# Computation.net
KiCad netlist of a schematic drawn in Altium Designer
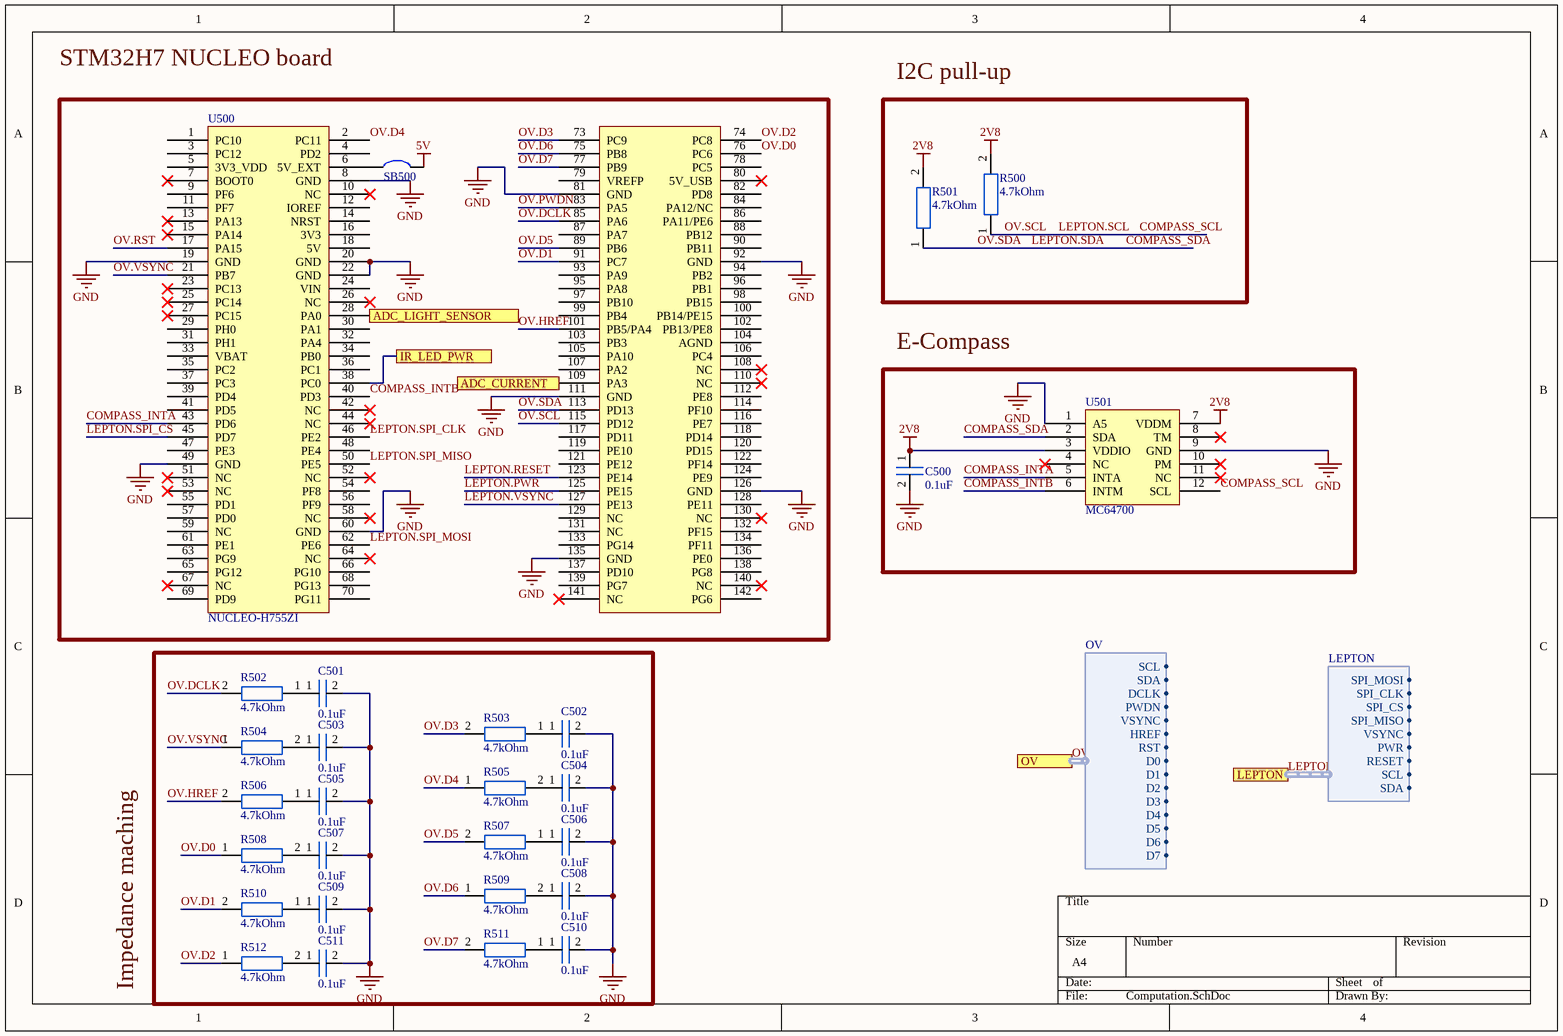
[diagram p0: Computation.SchDoc]

(export (version "E")
  (design (tool "Eeschema 10.0.6"))
  (components
    (comp (ref "C500")
      (value "0.1uF")
      (footprint "0402_footprint")
      (description "0402 capacitor")
      (libsource (lib "Schlib1") (part "Capacitor_0402"))
    )
    (comp (ref "C501")
      (value "0.1uF")
      (footprint "0402_footprint")
      (description "0402 capacitor")
      (libsource (lib "Schlib1") (part "Capacitor_0402"))
    )
    (comp (ref "C502")
      (value "0.1uF")
      (footprint "0402_footprint")
      (description "0402 capacitor")
      (libsource (lib "Schlib1") (part "Capacitor_0402"))
    )
    (comp (ref "C503")
      (value "0.1uF")
      (footprint "0402_footprint")
      (description "0402 capacitor")
      (libsource (lib "Schlib1") (part "Capacitor_0402"))
    )
    (comp (ref "C504")
      (value "0.1uF")
      (footprint "0402_footprint")
      (description "0402 capacitor")
      (libsource (lib "Schlib1") (part "Capacitor_0402"))
    )
    (comp (ref "C505")
      (value "0.1uF")
      (footprint "0402_footprint")
      (description "0402 capacitor")
      (libsource (lib "Schlib1") (part "Capacitor_0402"))
    )
    (comp (ref "C506")
      (value "0.1uF")
      (footprint "0402_footprint")
      (description "0402 capacitor")
      (libsource (lib "Schlib1") (part "Capacitor_0402"))
    )
    (comp (ref "C507")
      (value "0.1uF")
      (footprint "0402_footprint")
      (description "0402 capacitor")
      (libsource (lib "Schlib1") (part "Capacitor_0402"))
    )
    (comp (ref "C508")
      (value "0.1uF")
      (footprint "0402_footprint")
      (description "0402 capacitor")
      (libsource (lib "Schlib1") (part "Capacitor_0402"))
    )
    (comp (ref "C509")
      (value "0.1uF")
      (footprint "0402_footprint")
      (description "0402 capacitor")
      (libsource (lib "Schlib1") (part "Capacitor_0402"))
    )
    (comp (ref "C510")
      (value "0.1uF")
      (footprint "0402_footprint")
      (description "0402 capacitor")
      (libsource (lib "Schlib1") (part "Capacitor_0402"))
    )
    (comp (ref "C511")
      (value "0.1uF")
      (footprint "0402_footprint")
      (description "0402 capacitor")
      (libsource (lib "Schlib1") (part "Capacitor_0402"))
    )
    (comp (ref "R500")
      (value "4.7kOhm")
      (footprint "0402_footprint")
      (description "0402 resistor")
      (libsource (lib "Schlib1") (part "Resistor_0402"))
    )
    (comp (ref "R501")
      (value "4.7kOhm")
      (footprint "0402_footprint")
      (description "0402 resistor")
      (libsource (lib "Schlib1") (part "Resistor_0402"))
    )
    (comp (ref "R502")
      (value "4.7kOhm")
      (footprint "0402_footprint")
      (description "0402 resistor")
      (libsource (lib "Schlib1") (part "Resistor_0402"))
    )
    (comp (ref "R503")
      (value "4.7kOhm")
      (footprint "0402_footprint")
      (description "0402 resistor")
      (libsource (lib "Schlib1") (part "Resistor_0402"))
    )
    (comp (ref "R504")
      (value "4.7kOhm")
      (footprint "0402_footprint")
      (description "0402 resistor")
      (libsource (lib "Schlib1") (part "Resistor_0402"))
    )
    (comp (ref "R505")
      (value "4.7kOhm")
      (footprint "0402_footprint")
      (description "0402 resistor")
      (libsource (lib "Schlib1") (part "Resistor_0402"))
    )
    (comp (ref "R506")
      (value "4.7kOhm")
      (footprint "0402_footprint")
      (description "0402 resistor")
      (libsource (lib "Schlib1") (part "Resistor_0402"))
    )
    (comp (ref "R507")
      (value "4.7kOhm")
      (footprint "0402_footprint")
      (description "0402 resistor")
      (libsource (lib "Schlib1") (part "Resistor_0402"))
    )
    (comp (ref "R508")
      (value "4.7kOhm")
      (footprint "0402_footprint")
      (description "0402 resistor")
      (libsource (lib "Schlib1") (part "Resistor_0402"))
    )
    (comp (ref "R509")
      (value "4.7kOhm")
      (footprint "0402_footprint")
      (description "0402 resistor")
      (libsource (lib "Schlib1") (part "Resistor_0402"))
    )
    (comp (ref "R510")
      (value "4.7kOhm")
      (footprint "0402_footprint")
      (description "0402 resistor")
      (libsource (lib "Schlib1") (part "Resistor_0402"))
    )
    (comp (ref "R511")
      (value "4.7kOhm")
      (footprint "0402_footprint")
      (description "0402 resistor")
      (libsource (lib "Schlib1") (part "Resistor_0402"))
    )
    (comp (ref "R512")
      (value "4.7kOhm")
      (footprint "0402_footprint")
      (description "0402 resistor")
      (libsource (lib "Schlib1") (part "Resistor_0402"))
    )
    (comp (ref "SB500")
      (value "Solder_bridge")
      (footprint "SOLDER_BRIDGE")
      (libsource (lib "Schlib1") (part "Solder_bridge"))
    )
    (comp (ref "U500")
      (value "NUCLEO-H755ZI")
      (footprint "H7/H5_NUCLEO_SHIELD")
      (description "https://www.st.com/en/evaluation-tools/nucleo-h755zi-q.html#documentation")
      (libsource (lib "Schlib1") (part "NUCLEO-H755ZI"))
    )
    (comp (ref "U501")
      (value "MC64700")
      (footprint "MC6470")
      (description "6 axis accelerometer + magnetometer")
      (libsource (lib "Schlib1") (part "MC64700"))
    )
  )
  (nets
    (net (code "3") (name "/ADC_CURRENT") (class "Default")
      (node (ref "U500") (pin "109") (pinfunction "PA3_109") (pintype "passive"))
    )
    (net (code "4") (name "/ADC_LIGHT_SENSOR") (class "Default")
      (node (ref "U500") (pin "28") (pinfunction "PA0_28") (pintype "passive"))
    )
    (net (code "5") (name "/COMPASS_INTA") (class "Default")
      (node (ref "U500") (pin "43") (pinfunction "PD6_43") (pintype "passive"))
      (node (ref "U501") (pin "5") (pinfunction "INTA_5") (pintype "passive"))
    )
    (net (code "6") (name "/COMPASS_INTB") (class "Default")
      (node (ref "U500") (pin "40") (pinfunction "PD3_40") (pintype "passive"))
      (node (ref "U501") (pin "6") (pinfunction "INTM_6") (pintype "passive"))
    )
    (net (code "7") (name "/COMPASS_SCL") (class "Default")
      (node (ref "R500") (pin "1") (pinfunction "1_1") (pintype "passive"))
      (node (ref "U500") (pin "115") (pinfunction "PD12_115") (pintype "passive"))
      (node (ref "U501") (pin "12") (pinfunction "SCL_12") (pintype "passive"))
    )
    (net (code "8") (name "/COMPASS_SDA") (class "Default")
      (node (ref "R501") (pin "1") (pinfunction "1_1") (pintype "passive"))
      (node (ref "U500") (pin "113") (pinfunction "PD13_113") (pintype "passive"))
      (node (ref "U501") (pin "2") (pinfunction "SDA_2") (pintype "passive"))
    )
    (net (code "9") (name "/IR_LED_PWR") (class "Default")
      (node (ref "U500") (pin "38") (pinfunction "PC0_38") (pintype "passive"))
    )
    (net (code "10") (name "/LEPTON.PWR") (class "Default")
      (node (ref "U500") (pin "125") (pinfunction "PE15_125") (pintype "passive"))
    )
    (net (code "11") (name "/LEPTON.RESET") (class "Default")
      (node (ref "U500") (pin "123") (pinfunction "PE14_123") (pintype "passive"))
    )
    (net (code "12") (name "/LEPTON.SPI_CLK") (class "Default")
      (node (ref "U500") (pin "46") (pinfunction "PE2_46") (pintype "passive"))
    )
    (net (code "13") (name "/LEPTON.SPI_CS") (class "Default")
      (node (ref "U500") (pin "45") (pinfunction "PD7_45") (pintype "passive"))
    )
    (net (code "14") (name "/LEPTON.SPI_MISO") (class "Default")
      (node (ref "U500") (pin "50") (pinfunction "PE5_50") (pintype "passive"))
    )
    (net (code "15") (name "/LEPTON.SPI_MOSI") (class "Default")
      (node (ref "U500") (pin "62") (pinfunction "PE6_62") (pintype "passive"))
    )
    (net (code "16") (name "/LEPTON.VSYNC") (class "Default")
      (node (ref "U500") (pin "127") (pinfunction "PE13_127") (pintype "passive"))
    )
    (net (code "18") (name "/OV.D0") (class "Default")
      (node (ref "R508") (pin "1") (pinfunction "1_1") (pintype "passive"))
      (node (ref "U500") (pin "76") (pinfunction "PC6_76") (pintype "passive"))
    )
    (net (code "19") (name "/OV.D1") (class "Default")
      (node (ref "R510") (pin "2") (pinfunction "2_2") (pintype "passive"))
      (node (ref "U500") (pin "91") (pinfunction "PC7_91") (pintype "passive"))
    )
    (net (code "20") (name "/OV.D2") (class "Default")
      (node (ref "R512") (pin "1") (pinfunction "1_1") (pintype "passive"))
      (node (ref "U500") (pin "74") (pinfunction "PC8_74") (pintype "passive"))
    )
    (net (code "21") (name "/OV.D3") (class "Default")
      (node (ref "R503") (pin "2") (pinfunction "2_2") (pintype "passive"))
      (node (ref "U500") (pin "73") (pinfunction "PC9_73") (pintype "passive"))
    )
    (net (code "22") (name "/OV.D4") (class "Default")
      (node (ref "R505") (pin "1") (pinfunction "1_1") (pintype "passive"))
      (node (ref "U500") (pin "2") (pinfunction "PC11_2") (pintype "passive"))
    )
    (net (code "23") (name "/OV.D5") (class "Default")
      (node (ref "R507") (pin "2") (pinfunction "2_2") (pintype "passive"))
      (node (ref "U500") (pin "89") (pinfunction "PB6_89") (pintype "passive"))
    )
    (net (code "24") (name "/OV.D6") (class "Default")
      (node (ref "R509") (pin "1") (pinfunction "1_1") (pintype "passive"))
      (node (ref "U500") (pin "75") (pinfunction "PB8_75") (pintype "passive"))
    )
    (net (code "25") (name "/OV.D7") (class "Default")
      (node (ref "R511") (pin "2") (pinfunction "2_2") (pintype "passive"))
      (node (ref "U500") (pin "77") (pinfunction "PB9_77") (pintype "passive"))
    )
    (net (code "26") (name "/OV.DCLK") (class "Default")
      (node (ref "R502") (pin "2") (pinfunction "2_2") (pintype "passive"))
      (node (ref "U500") (pin "85") (pinfunction "PA6_85") (pintype "passive"))
    )
    (net (code "27") (name "/OV.HREF") (class "Default")
      (node (ref "R506") (pin "2") (pinfunction "2_2") (pintype "passive"))
      (node (ref "U500") (pin "101") (pinfunction "PB5/PA4_101") (pintype "passive"))
    )
    (net (code "28") (name "/OV.PWDN") (class "Default")
      (node (ref "U500") (pin "83") (pinfunction "PA5_83") (pintype "passive"))
    )
    (net (code "29") (name "/OV.RST") (class "Default")
      (node (ref "U500") (pin "17") (pinfunction "PA15_17") (pintype "passive"))
    )
    (net (code "30") (name "/OV.VSYNC") (class "Default")
      (node (ref "R504") (pin "1") (pinfunction "1_1") (pintype "passive"))
      (node (ref "U500") (pin "21") (pinfunction "PB7_21") (pintype "passive"))
    )
    (net (code "32") (name "2V8") (class "Default")
      (node (ref "C500") (pin "1") (pinfunction "1_1") (pintype "passive"))
      (node (ref "R500") (pin "2") (pinfunction "2_2") (pintype "passive"))
      (node (ref "R501") (pin "2") (pinfunction "2_2") (pintype "passive"))
      (node (ref "U501") (pin "3") (pinfunction "VDDIO_3") (pintype "passive"))
      (node (ref "U501") (pin "7") (pinfunction "VDDM_7") (pintype "passive"))
    )
    (net (code "33") (name "5V") (class "Default")
      (node (ref "SB500") (pin "2") (pinfunction "2_2") (pintype "passive"))
    )
    (net (code "34") (name "GND") (class "Default")
      (node (ref "C500") (pin "2") (pinfunction "2_2") (pintype "passive"))
      (node (ref "C501") (pin "2") (pinfunction "2_2") (pintype "passive"))
      (node (ref "C502") (pin "2") (pinfunction "2_2") (pintype "passive"))
      (node (ref "C503") (pin "2") (pinfunction "2_2") (pintype "passive"))
      (node (ref "C504") (pin "2") (pinfunction "2_2") (pintype "passive"))
      (node (ref "C505") (pin "2") (pinfunction "2_2") (pintype "passive"))
      (node (ref "C506") (pin "2") (pinfunction "2_2") (pintype "passive"))
      (node (ref "C507") (pin "2") (pinfunction "2_2") (pintype "passive"))
      (node (ref "C508") (pin "2") (pinfunction "2_2") (pintype "passive"))
      (node (ref "C509") (pin "2") (pinfunction "2_2") (pintype "passive"))
      (node (ref "C510") (pin "2") (pinfunction "2_2") (pintype "passive"))
      (node (ref "C511") (pin "2") (pinfunction "2_2") (pintype "passive"))
      (node (ref "U500") (pin "111") (pinfunction "GND_111") (pintype "passive"))
      (node (ref "U500") (pin "126") (pinfunction "GND_126") (pintype "passive"))
      (node (ref "U500") (pin "135") (pinfunction "GND_135") (pintype "passive"))
      (node (ref "U500") (pin "19") (pinfunction "GND_19") (pintype "passive"))
      (node (ref "U500") (pin "20") (pinfunction "GND_20") (pintype "passive"))
      (node (ref "U500") (pin "22") (pinfunction "GND_22") (pintype "passive"))
      (node (ref "U500") (pin "49") (pinfunction "GND_49") (pintype "passive"))
      (node (ref "U500") (pin "60") (pinfunction "GND_60") (pintype "passive"))
      (node (ref "U500") (pin "8") (pinfunction "GND_8") (pintype "passive"))
      (node (ref "U500") (pin "81") (pinfunction "GND_81") (pintype "passive"))
      (node (ref "U500") (pin "92") (pinfunction "GND_92") (pintype "passive"))
      (node (ref "U501") (pin "1") (pinfunction "A5_1") (pintype "passive"))
      (node (ref "U501") (pin "9") (pinfunction "GND_9") (pintype "passive"))
    )
    (net (code "35") (name "Net-(C501-Pad1)") (class "Default")
      (node (ref "C501") (pin "1") (pinfunction "1_1") (pintype "passive"))
      (node (ref "R502") (pin "1") (pinfunction "1_1") (pintype "passive"))
    )
    (net (code "36") (name "Net-(C502-Pad1)") (class "Default")
      (node (ref "C502") (pin "1") (pinfunction "1_1") (pintype "passive"))
      (node (ref "R503") (pin "1") (pinfunction "1_1") (pintype "passive"))
    )
    (net (code "37") (name "Net-(C503-Pad1)") (class "Default")
      (node (ref "C503") (pin "1") (pinfunction "1_1") (pintype "passive"))
      (node (ref "R504") (pin "2") (pinfunction "2_2") (pintype "passive"))
    )
    (net (code "38") (name "Net-(C504-Pad1)") (class "Default")
      (node (ref "C504") (pin "1") (pinfunction "1_1") (pintype "passive"))
      (node (ref "R505") (pin "2") (pinfunction "2_2") (pintype "passive"))
    )
    (net (code "39") (name "Net-(C505-Pad1)") (class "Default")
      (node (ref "C505") (pin "1") (pinfunction "1_1") (pintype "passive"))
      (node (ref "R506") (pin "1") (pinfunction "1_1") (pintype "passive"))
    )
    (net (code "40") (name "Net-(C506-Pad1)") (class "Default")
      (node (ref "C506") (pin "1") (pinfunction "1_1") (pintype "passive"))
      (node (ref "R507") (pin "1") (pinfunction "1_1") (pintype "passive"))
    )
    (net (code "41") (name "Net-(C507-Pad1)") (class "Default")
      (node (ref "C507") (pin "1") (pinfunction "1_1") (pintype "passive"))
      (node (ref "R508") (pin "2") (pinfunction "2_2") (pintype "passive"))
    )
    (net (code "42") (name "Net-(C508-Pad1)") (class "Default")
      (node (ref "C508") (pin "1") (pinfunction "1_1") (pintype "passive"))
      (node (ref "R509") (pin "2") (pinfunction "2_2") (pintype "passive"))
    )
    (net (code "43") (name "Net-(C509-Pad1)") (class "Default")
      (node (ref "C509") (pin "1") (pinfunction "1_1") (pintype "passive"))
      (node (ref "R510") (pin "1") (pinfunction "1_1") (pintype "passive"))
    )
    (net (code "44") (name "Net-(C510-Pad1)") (class "Default")
      (node (ref "C510") (pin "1") (pinfunction "1_1") (pintype "passive"))
      (node (ref "R511") (pin "1") (pinfunction "1_1") (pintype "passive"))
    )
    (net (code "45") (name "Net-(C511-Pad1)") (class "Default")
      (node (ref "C511") (pin "1") (pinfunction "1_1") (pintype "passive"))
      (node (ref "R512") (pin "2") (pinfunction "2_2") (pintype "passive"))
    )
    (net (code "46") (name "Net-(U500-5V_EXT)") (class "Default")
      (node (ref "SB500") (pin "1") (pinfunction "1_1") (pintype "passive"))
      (node (ref "U500") (pin "6") (pinfunction "5V_EXT_6") (pintype "passive"))
    )
    (net (code "47") (name "unconnected-(U500-3V3-Pad16)") (class "Default")
      (node (ref "U500") (pin "16") (pinfunction "3V3_16") (pintype "passive"))
    )
    (net (code "48") (name "unconnected-(U500-3V3_VDD-Pad5)") (class "Default")
      (node (ref "U500") (pin "5") (pinfunction "3V3_VDD_5") (pintype "passive"))
    )
    (net (code "49") (name "unconnected-(U500-5V-Pad18)") (class "Default")
      (node (ref "U500") (pin "18") (pinfunction "5V_18") (pintype "passive"))
    )
    (net (code "50") (name "unconnected-(U500-5V_USB-Pad80)") (class "Default")
      (node (ref "U500") (pin "80") (pinfunction "5V_USB_80") (pintype "passive+no_connect"))
    )
    (net (code "51") (name "unconnected-(U500-AGND-Pad104)") (class "Default")
      (node (ref "U500") (pin "104") (pinfunction "AGND_104") (pintype "passive"))
    )
    (net (code "52") (name "unconnected-(U500-BOOT0-Pad7)") (class "Default")
      (node (ref "U500") (pin "7") (pinfunction "BOOT0_7") (pintype "passive+no_connect"))
    )
    (net (code "53") (name "unconnected-(U500-IOREF-Pad12)") (class "Default")
      (node (ref "U500") (pin "12") (pinfunction "IOREF_12") (pintype "passive"))
    )
    (net (code "54") (name "unconnected-(U500-NC-Pad10)") (class "Default")
      (node (ref "U500") (pin "10") (pinfunction "NC_10") (pintype "passive+no_connect"))
    )
    (net (code "55") (name "unconnected-(U500-NC-Pad26)") (class "Default")
      (node (ref "U500") (pin "26") (pinfunction "NC_26") (pintype "passive+no_connect"))
    )
    (net (code "56") (name "unconnected-(U500-NC-Pad42)") (class "Default")
      (node (ref "U500") (pin "42") (pinfunction "NC_42") (pintype "passive+no_connect"))
    )
    (net (code "57") (name "unconnected-(U500-NC-Pad44)") (class "Default")
      (node (ref "U500") (pin "44") (pinfunction "NC_44") (pintype "passive+no_connect"))
    )
    (net (code "58") (name "unconnected-(U500-NC-Pad51)") (class "Default")
      (node (ref "U500") (pin "51") (pinfunction "NC_51") (pintype "passive+no_connect"))
    )
    (net (code "59") (name "unconnected-(U500-NC-Pad52)") (class "Default")
      (node (ref "U500") (pin "52") (pinfunction "NC_52") (pintype "passive+no_connect"))
    )
    (net (code "60") (name "unconnected-(U500-NC-Pad53)") (class "Default")
      (node (ref "U500") (pin "53") (pinfunction "NC_53") (pintype "passive+no_connect"))
    )
    (net (code "61") (name "unconnected-(U500-NC-Pad58)") (class "Default")
      (node (ref "U500") (pin "58") (pinfunction "NC_58") (pintype "passive+no_connect"))
    )
    (net (code "62") (name "unconnected-(U500-NC-Pad59)") (class "Default")
      (node (ref "U500") (pin "59") (pinfunction "NC_59") (pintype "passive"))
    )
    (net (code "63") (name "unconnected-(U500-NC-Pad64)") (class "Default")
      (node (ref "U500") (pin "64") (pinfunction "NC_64") (pintype "passive+no_connect"))
    )
    (net (code "64") (name "unconnected-(U500-NC-Pad67)") (class "Default")
      (node (ref "U500") (pin "67") (pinfunction "NC_67") (pintype "passive+no_connect"))
    )
    (net (code "65") (name "unconnected-(U500-NC-Pad108)") (class "Default")
      (node (ref "U500") (pin "108") (pinfunction "NC_108") (pintype "passive+no_connect"))
    )
    (net (code "66") (name "unconnected-(U500-NC-Pad110)") (class "Default")
      (node (ref "U500") (pin "110") (pinfunction "NC_110") (pintype "passive+no_connect"))
    )
    (net (code "67") (name "unconnected-(U500-NC-Pad129)") (class "Default")
      (node (ref "U500") (pin "129") (pinfunction "NC_129") (pintype "passive"))
    )
    (net (code "68") (name "unconnected-(U500-NC-Pad130)") (class "Default")
      (node (ref "U500") (pin "130") (pinfunction "NC_130") (pintype "passive+no_connect"))
    )
    (net (code "69") (name "unconnected-(U500-NC-Pad131)") (class "Default")
      (node (ref "U500") (pin "131") (pinfunction "NC_131") (pintype "passive"))
    )
    (net (code "70") (name "unconnected-(U500-NC-Pad140)") (class "Default")
      (node (ref "U500") (pin "140") (pinfunction "NC_140") (pintype "passive+no_connect"))
    )
    (net (code "71") (name "unconnected-(U500-NC-Pad141)") (class "Default")
      (node (ref "U500") (pin "141") (pinfunction "NC_141") (pintype "passive+no_connect"))
    )
    (net (code "72") (name "unconnected-(U500-NRST-Pad14)") (class "Default")
      (node (ref "U500") (pin "14") (pinfunction "NRST_14") (pintype "passive"))
    )
    (net (code "73") (name "unconnected-(U500-PA1-Pad30)") (class "Default")
      (node (ref "U500") (pin "30") (pinfunction "PA1_30") (pintype "passive"))
    )
    (net (code "74") (name "unconnected-(U500-PA2-Pad107)") (class "Default")
      (node (ref "U500") (pin "107") (pinfunction "PA2_107") (pintype "passive"))
    )
    (net (code "75") (name "unconnected-(U500-PA4-Pad32)") (class "Default")
      (node (ref "U500") (pin "32") (pinfunction "PA4_32") (pintype "passive"))
    )
    (net (code "76") (name "unconnected-(U500-PA7-Pad87)") (class "Default")
      (node (ref "U500") (pin "87") (pinfunction "PA7_87") (pintype "passive"))
    )
    (net (code "77") (name "unconnected-(U500-PA8-Pad95)") (class "Default")
      (node (ref "U500") (pin "95") (pinfunction "PA8_95") (pintype "passive"))
    )
    (net (code "78") (name "unconnected-(U500-PA9-Pad93)") (class "Default")
      (node (ref "U500") (pin "93") (pinfunction "PA9_93") (pintype "passive"))
    )
    (net (code "79") (name "unconnected-(U500-PA10-Pad105)") (class "Default")
      (node (ref "U500") (pin "105") (pinfunction "PA10_105") (pintype "passive"))
    )
    (net (code "80") (name "unconnected-(U500-PA11{slash}PE6-Pad86)") (class "Default")
      (node (ref "U500") (pin "86") (pinfunction "PA11/PE6_86") (pintype "passive"))
    )
    (net (code "81") (name "unconnected-(U500-PA12{slash}NC-Pad84)") (class "Default")
      (node (ref "U500") (pin "84") (pinfunction "PA12/NC_84") (pintype "passive"))
    )
    (net (code "82") (name "unconnected-(U500-PA13-Pad13)") (class "Default")
      (node (ref "U500") (pin "13") (pinfunction "PA13_13") (pintype "passive+no_connect"))
    )
    (net (code "83") (name "unconnected-(U500-PA14-Pad15)") (class "Default")
      (node (ref "U500") (pin "15") (pinfunction "PA14_15") (pintype "passive+no_connect"))
    )
    (net (code "84") (name "unconnected-(U500-PB0-Pad34)") (class "Default")
      (node (ref "U500") (pin "34") (pinfunction "PB0_34") (pintype "passive"))
    )
    (net (code "85") (name "unconnected-(U500-PB1-Pad96)") (class "Default")
      (node (ref "U500") (pin "96") (pinfunction "PB1_96") (pintype "passive"))
    )
    (net (code "86") (name "unconnected-(U500-PB2-Pad94)") (class "Default")
      (node (ref "U500") (pin "94") (pinfunction "PB2_94") (pintype "passive"))
    )
    (net (code "87") (name "unconnected-(U500-PB3-Pad103)") (class "Default")
      (node (ref "U500") (pin "103") (pinfunction "PB3_103") (pintype "passive"))
    )
    (net (code "88") (name "unconnected-(U500-PB4-Pad99)") (class "Default")
      (node (ref "U500") (pin "99") (pinfunction "PB4_99") (pintype "passive"))
    )
    (net (code "89") (name "unconnected-(U500-PB10-Pad97)") (class "Default")
      (node (ref "U500") (pin "97") (pinfunction "PB10_97") (pintype "passive"))
    )
    (net (code "90") (name "unconnected-(U500-PB11-Pad90)") (class "Default")
      (node (ref "U500") (pin "90") (pinfunction "PB11_90") (pintype "passive"))
    )
    (net (code "91") (name "unconnected-(U500-PB12-Pad88)") (class "Default")
      (node (ref "U500") (pin "88") (pinfunction "PB12_88") (pintype "passive"))
    )
    (net (code "92") (name "unconnected-(U500-PB13{slash}PE8-Pad102)") (class "Default")
      (node (ref "U500") (pin "102") (pinfunction "PB13/PE8_102") (pintype "passive"))
    )
    (net (code "93") (name "unconnected-(U500-PB14{slash}PE15-Pad100)") (class "Default")
      (node (ref "U500") (pin "100") (pinfunction "PB14/PE15_100") (pintype "passive"))
    )
    (net (code "94") (name "unconnected-(U500-PB15-Pad98)") (class "Default")
      (node (ref "U500") (pin "98") (pinfunction "PB15_98") (pintype "passive"))
    )
    (net (code "95") (name "unconnected-(U500-PC1-Pad36)") (class "Default")
      (node (ref "U500") (pin "36") (pinfunction "PC1_36") (pintype "passive"))
    )
    (net (code "96") (name "unconnected-(U500-PC2-Pad35)") (class "Default")
      (node (ref "U500") (pin "35") (pinfunction "PC2_35") (pintype "passive"))
    )
    (net (code "97") (name "unconnected-(U500-PC3-Pad37)") (class "Default")
      (node (ref "U500") (pin "37") (pinfunction "PC3_37") (pintype "passive"))
    )
    (net (code "98") (name "unconnected-(U500-PC4-Pad106)") (class "Default")
      (node (ref "U500") (pin "106") (pinfunction "PC4_106") (pintype "passive"))
    )
    (net (code "99") (name "unconnected-(U500-PC5-Pad78)") (class "Default")
      (node (ref "U500") (pin "78") (pinfunction "PC5_78") (pintype "passive"))
    )
    (net (code "100") (name "unconnected-(U500-PC10-Pad1)") (class "Default")
      (node (ref "U500") (pin "1") (pinfunction "PC10_1") (pintype "passive"))
    )
    (net (code "101") (name "unconnected-(U500-PC12-Pad3)") (class "Default")
      (node (ref "U500") (pin "3") (pinfunction "PC12_3") (pintype "passive"))
    )
    (net (code "102") (name "unconnected-(U500-PC13-Pad23)") (class "Default")
      (node (ref "U500") (pin "23") (pinfunction "PC13_23") (pintype "passive+no_connect"))
    )
    (net (code "103") (name "unconnected-(U500-PC14-Pad25)") (class "Default")
      (node (ref "U500") (pin "25") (pinfunction "PC14_25") (pintype "passive+no_connect"))
    )
    (net (code "104") (name "unconnected-(U500-PC15-Pad27)") (class "Default")
      (node (ref "U500") (pin "27") (pinfunction "PC15_27") (pintype "passive+no_connect"))
    )
    (net (code "105") (name "unconnected-(U500-PD0-Pad57)") (class "Default")
      (node (ref "U500") (pin "57") (pinfunction "PD0_57") (pintype "passive"))
    )
    (net (code "106") (name "unconnected-(U500-PD1-Pad55)") (class "Default")
      (node (ref "U500") (pin "55") (pinfunction "PD1_55") (pintype "passive"))
    )
    (net (code "107") (name "unconnected-(U500-PD2-Pad4)") (class "Default")
      (node (ref "U500") (pin "4") (pinfunction "PD2_4") (pintype "passive"))
    )
    (net (code "108") (name "unconnected-(U500-PD4-Pad39)") (class "Default")
      (node (ref "U500") (pin "39") (pinfunction "PD4_39") (pintype "passive"))
    )
    (net (code "109") (name "unconnected-(U500-PD5-Pad41)") (class "Default")
      (node (ref "U500") (pin "41") (pinfunction "PD5_41") (pintype "passive"))
    )
    (net (code "110") (name "unconnected-(U500-PD8-Pad82)") (class "Default")
      (node (ref "U500") (pin "82") (pinfunction "PD8_82") (pintype "passive"))
    )
    (net (code "111") (name "unconnected-(U500-PD9-Pad69)") (class "Default")
      (node (ref "U500") (pin "69") (pinfunction "PD9_69") (pintype "passive"))
    )
    (net (code "112") (name "unconnected-(U500-PD10-Pad137)") (class "Default")
      (node (ref "U500") (pin "137") (pinfunction "PD10_137") (pintype "passive"))
    )
    (net (code "113") (name "unconnected-(U500-PD11-Pad117)") (class "Default")
      (node (ref "U500") (pin "117") (pinfunction "PD11_117") (pintype "passive"))
    )
    (net (code "114") (name "unconnected-(U500-PD14-Pad118)") (class "Default")
      (node (ref "U500") (pin "118") (pinfunction "PD14_118") (pintype "passive"))
    )
    (net (code "115") (name "unconnected-(U500-PD15-Pad120)") (class "Default")
      (node (ref "U500") (pin "120") (pinfunction "PD15_120") (pintype "passive"))
    )
    (net (code "116") (name "unconnected-(U500-PE0-Pad136)") (class "Default")
      (node (ref "U500") (pin "136") (pinfunction "PE0_136") (pintype "passive"))
    )
    (net (code "117") (name "unconnected-(U500-PE1-Pad61)") (class "Default")
      (node (ref "U500") (pin "61") (pinfunction "PE1_61") (pintype "passive"))
    )
    (net (code "118") (name "unconnected-(U500-PE3-Pad47)") (class "Default")
      (node (ref "U500") (pin "47") (pinfunction "PE3_47") (pintype "passive"))
    )
    (net (code "119") (name "unconnected-(U500-PE4-Pad48)") (class "Default")
      (node (ref "U500") (pin "48") (pinfunction "PE4_48") (pintype "passive"))
    )
    (net (code "120") (name "unconnected-(U500-PE7-Pad116)") (class "Default")
      (node (ref "U500") (pin "116") (pinfunction "PE7_116") (pintype "passive"))
    )
    (net (code "121") (name "unconnected-(U500-PE8-Pad112)") (class "Default")
      (node (ref "U500") (pin "112") (pinfunction "PE8_112") (pintype "passive"))
    )
    (net (code "122") (name "unconnected-(U500-PE9-Pad124)") (class "Default")
      (node (ref "U500") (pin "124") (pinfunction "PE9_124") (pintype "passive"))
    )
    (net (code "123") (name "unconnected-(U500-PE10-Pad119)") (class "Default")
      (node (ref "U500") (pin "119") (pinfunction "PE10_119") (pintype "passive"))
    )
    (net (code "124") (name "unconnected-(U500-PE11-Pad128)") (class "Default")
      (node (ref "U500") (pin "128") (pinfunction "PE11_128") (pintype "passive"))
    )
    (net (code "125") (name "unconnected-(U500-PE12-Pad121)") (class "Default")
      (node (ref "U500") (pin "121") (pinfunction "PE12_121") (pintype "passive"))
    )
    (net (code "126") (name "unconnected-(U500-PF6-Pad9)") (class "Default")
      (node (ref "U500") (pin "9") (pinfunction "PF6_9") (pintype "passive"))
    )
    (net (code "127") (name "unconnected-(U500-PF7-Pad11)") (class "Default")
      (node (ref "U500") (pin "11") (pinfunction "PF7_11") (pintype "passive"))
    )
    (net (code "128") (name "unconnected-(U500-PF8-Pad54)") (class "Default")
      (node (ref "U500") (pin "54") (pinfunction "PF8_54") (pintype "passive"))
    )
    (net (code "129") (name "unconnected-(U500-PF9-Pad56)") (class "Default")
      (node (ref "U500") (pin "56") (pinfunction "PF9_56") (pintype "passive"))
    )
    (net (code "130") (name "unconnected-(U500-PF10-Pad114)") (class "Default")
      (node (ref "U500") (pin "114") (pinfunction "PF10_114") (pintype "passive"))
    )
    (net (code "131") (name "unconnected-(U500-PF11-Pad134)") (class "Default")
      (node (ref "U500") (pin "134") (pinfunction "PF11_134") (pintype "passive"))
    )
    (net (code "132") (name "unconnected-(U500-PF14-Pad122)") (class "Default")
      (node (ref "U500") (pin "122") (pinfunction "PF14_122") (pintype "passive"))
    )
    (net (code "133") (name "unconnected-(U500-PF15-Pad132)") (class "Default")
      (node (ref "U500") (pin "132") (pinfunction "PF15_132") (pintype "passive"))
    )
    (net (code "134") (name "unconnected-(U500-PG6-Pad142)") (class "Default")
      (node (ref "U500") (pin "142") (pinfunction "PG6_142") (pintype "passive"))
    )
    (net (code "135") (name "unconnected-(U500-PG7-Pad139)") (class "Default")
      (node (ref "U500") (pin "139") (pinfunction "PG7_139") (pintype "passive"))
    )
    (net (code "136") (name "unconnected-(U500-PG8-Pad138)") (class "Default")
      (node (ref "U500") (pin "138") (pinfunction "PG8_138") (pintype "passive"))
    )
    (net (code "137") (name "unconnected-(U500-PG9-Pad63)") (class "Default")
      (node (ref "U500") (pin "63") (pinfunction "PG9_63") (pintype "passive"))
    )
    (net (code "138") (name "unconnected-(U500-PG10-Pad66)") (class "Default")
      (node (ref "U500") (pin "66") (pinfunction "PG10_66") (pintype "passive"))
    )
    (net (code "139") (name "unconnected-(U500-PG11-Pad70)") (class "Default")
      (node (ref "U500") (pin "70") (pinfunction "PG11_70") (pintype "passive"))
    )
    (net (code "140") (name "unconnected-(U500-PG12-Pad65)") (class "Default")
      (node (ref "U500") (pin "65") (pinfunction "PG12_65") (pintype "passive"))
    )
    (net (code "141") (name "unconnected-(U500-PG13-Pad68)") (class "Default")
      (node (ref "U500") (pin "68") (pinfunction "PG13_68") (pintype "passive"))
    )
    (net (code "142") (name "unconnected-(U500-PG14-Pad133)") (class "Default")
      (node (ref "U500") (pin "133") (pinfunction "PG14_133") (pintype "passive"))
    )
    (net (code "143") (name "unconnected-(U500-PH0-Pad29)") (class "Default")
      (node (ref "U500") (pin "29") (pinfunction "PH0_29") (pintype "passive"))
    )
    (net (code "144") (name "unconnected-(U500-PH1-Pad31)") (class "Default")
      (node (ref "U500") (pin "31") (pinfunction "PH1_31") (pintype "passive"))
    )
    (net (code "145") (name "unconnected-(U500-VBAT-Pad33)") (class "Default")
      (node (ref "U500") (pin "33") (pinfunction "VBAT_33") (pintype "passive"))
    )
    (net (code "146") (name "unconnected-(U500-VIN-Pad24)") (class "Default")
      (node (ref "U500") (pin "24") (pinfunction "VIN_24") (pintype "passive"))
    )
    (net (code "147") (name "unconnected-(U500-VREFP-Pad79)") (class "Default")
      (node (ref "U500") (pin "79") (pinfunction "VREFP_79") (pintype "passive"))
    )
    (net (code "148") (name "unconnected-(U501-NC-Pad4)") (class "Default")
      (node (ref "U501") (pin "4") (pinfunction "NC_4") (pintype "passive+no_connect"))
    )
    (net (code "149") (name "unconnected-(U501-NC-Pad11)") (class "Default")
      (node (ref "U501") (pin "11") (pinfunction "NC_11") (pintype "passive+no_connect"))
    )
    (net (code "150") (name "unconnected-(U501-PM-Pad10)") (class "Default")
      (node (ref "U501") (pin "10") (pinfunction "PM_10") (pintype "passive+no_connect"))
    )
    (net (code "151") (name "unconnected-(U501-TM-Pad8)") (class "Default")
      (node (ref "U501") (pin "8") (pinfunction "TM_8") (pintype "passive+no_connect"))
    )
  )
)
